# Input_v2_1.net
KiCad netlist of a schematic drawn in EAGLE
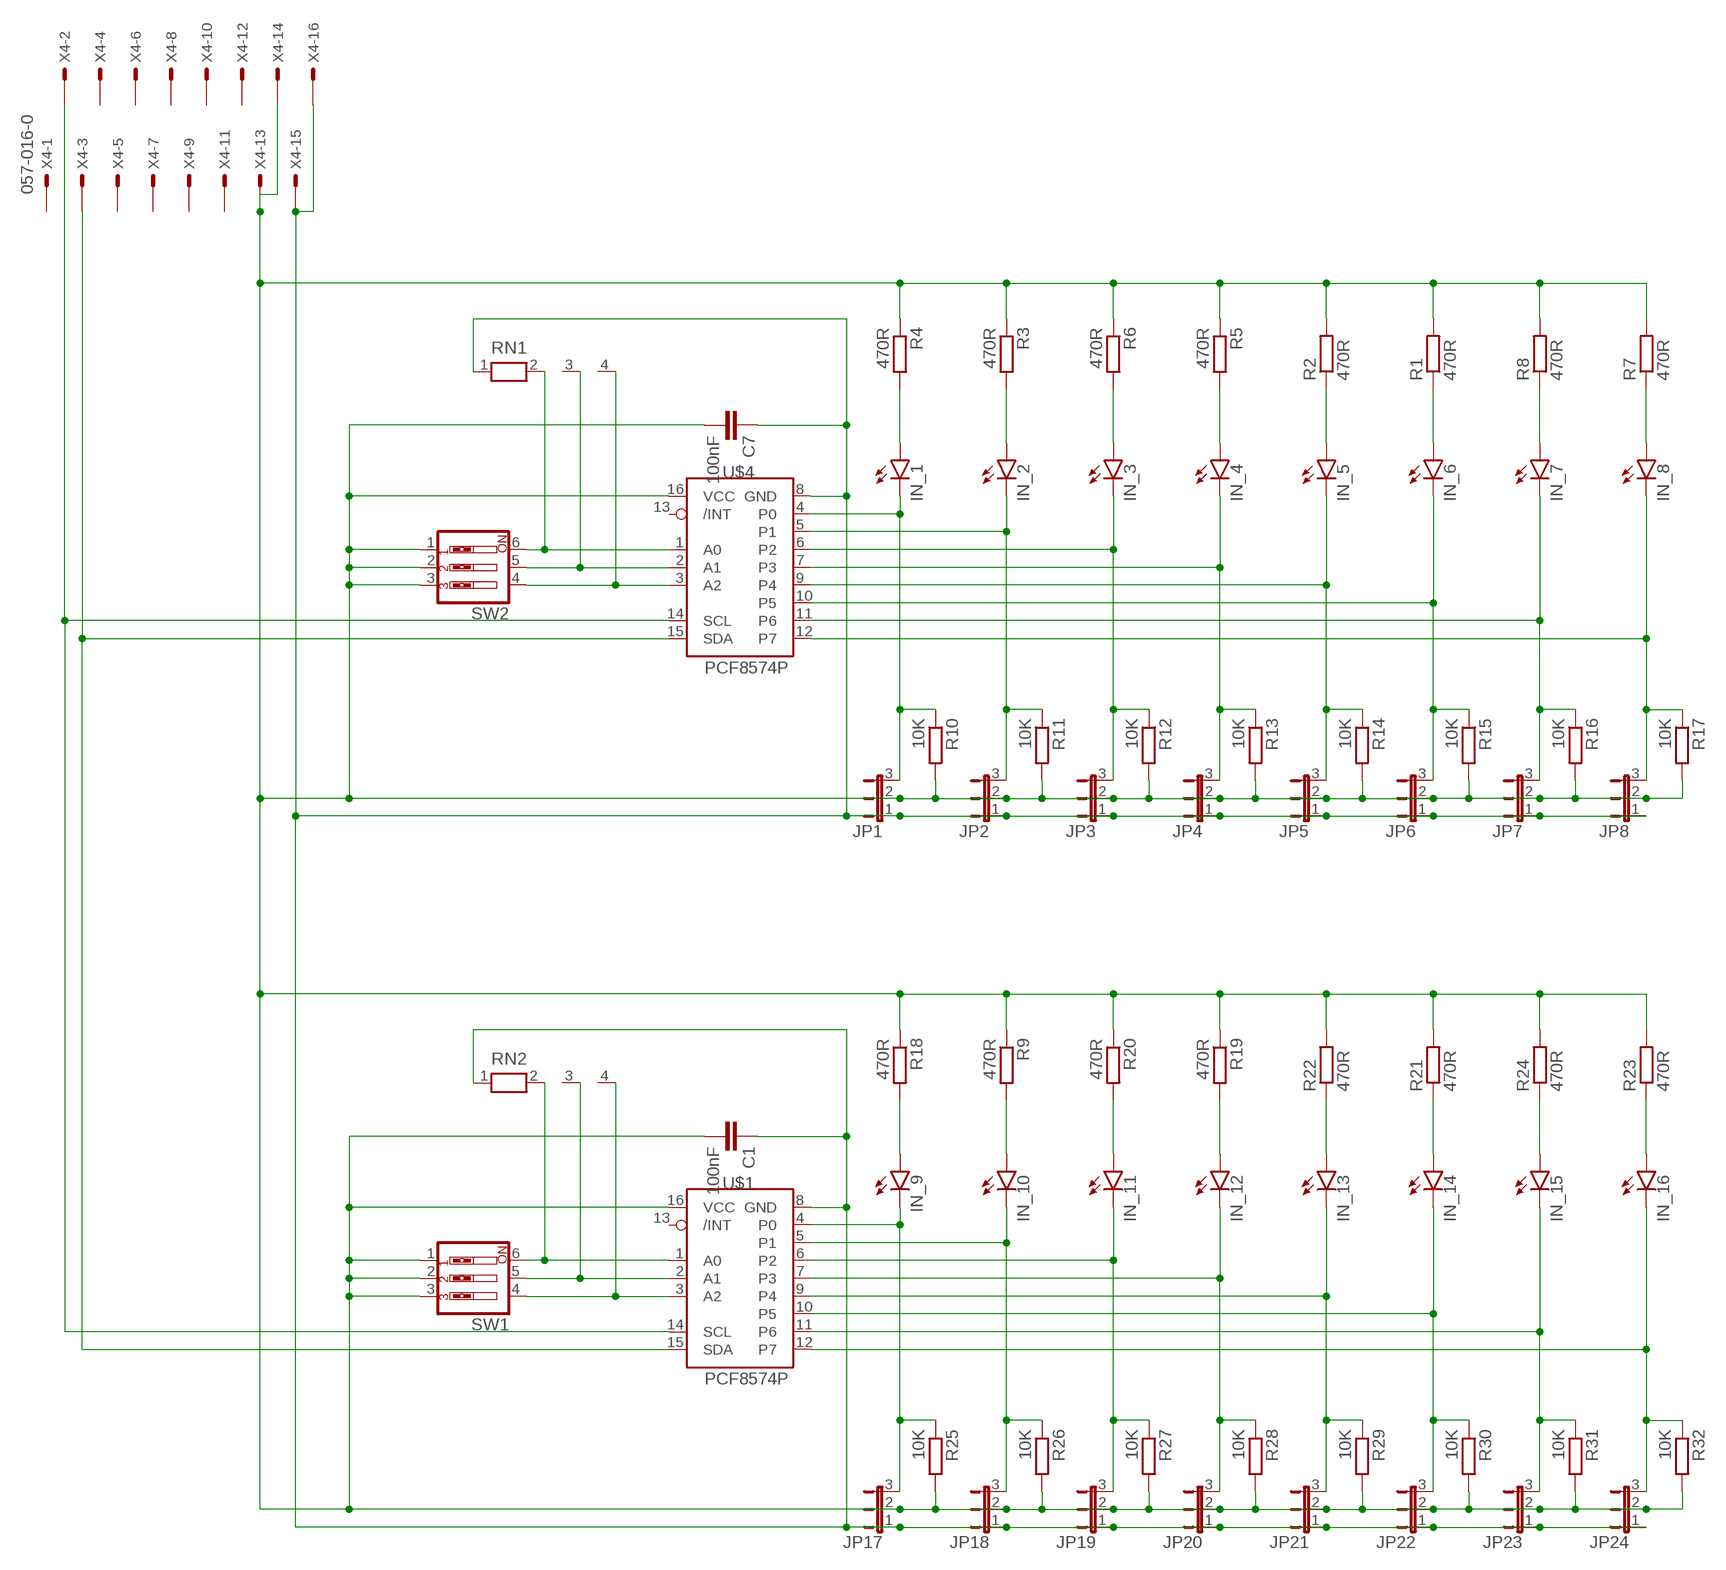
[diagram p0: schematic, sheet 1]

(export (version "E")
  (design (tool "Eeschema 10.0.6"))
  (components
    (comp (ref "C1")
      (value "100nF")
      (footprint "eagle-import:C025-024X044")
      (libsource (lib "eagle-import") (part "C-EU025-024X044"))
    )
    (comp (ref "C7")
      (value "100nF")
      (footprint "eagle-import:C025-024X044")
      (libsource (lib "eagle-import") (part "C-EU025-024X044"))
    )
    (comp (ref "IN_1")
      (value "LED3MM")
      (footprint "eagle-import:LED3MM")
      (libsource (lib "eagle-import") (part "LED3MM"))
    )
    (comp (ref "IN_2")
      (value "LED3MM")
      (footprint "eagle-import:LED3MM")
      (libsource (lib "eagle-import") (part "LED3MM"))
    )
    (comp (ref "IN_3")
      (value "LED3MM")
      (footprint "eagle-import:LED3MM")
      (libsource (lib "eagle-import") (part "LED3MM"))
    )
    (comp (ref "IN_4")
      (value "LED3MM")
      (footprint "eagle-import:LED3MM")
      (libsource (lib "eagle-import") (part "LED3MM"))
    )
    (comp (ref "IN_5")
      (value "LED3MM")
      (footprint "eagle-import:LED3MM")
      (libsource (lib "eagle-import") (part "LED3MM"))
    )
    (comp (ref "IN_6")
      (value "LED3MM")
      (footprint "eagle-import:LED3MM")
      (libsource (lib "eagle-import") (part "LED3MM"))
    )
    (comp (ref "IN_7")
      (value "LED3MM")
      (footprint "eagle-import:LED3MM")
      (libsource (lib "eagle-import") (part "LED3MM"))
    )
    (comp (ref "IN_8")
      (value "LED3MM")
      (footprint "eagle-import:LED3MM")
      (libsource (lib "eagle-import") (part "LED3MM"))
    )
    (comp (ref "IN_9")
      (value "LED3MM")
      (footprint "eagle-import:LED3MM")
      (libsource (lib "eagle-import") (part "LED3MM"))
    )
    (comp (ref "IN_10")
      (value "LED3MM")
      (footprint "eagle-import:LED3MM")
      (libsource (lib "eagle-import") (part "LED3MM"))
    )
    (comp (ref "IN_11")
      (value "LED3MM")
      (footprint "eagle-import:LED3MM")
      (libsource (lib "eagle-import") (part "LED3MM"))
    )
    (comp (ref "IN_12")
      (value "LED3MM")
      (footprint "eagle-import:LED3MM")
      (libsource (lib "eagle-import") (part "LED3MM"))
    )
    (comp (ref "IN_13")
      (value "LED3MM")
      (footprint "eagle-import:LED3MM")
      (libsource (lib "eagle-import") (part "LED3MM"))
    )
    (comp (ref "IN_14")
      (value "LED3MM")
      (footprint "eagle-import:LED3MM")
      (libsource (lib "eagle-import") (part "LED3MM"))
    )
    (comp (ref "IN_15")
      (value "LED3MM")
      (footprint "eagle-import:LED3MM")
      (libsource (lib "eagle-import") (part "LED3MM"))
    )
    (comp (ref "IN_16")
      (value "LED3MM")
      (footprint "eagle-import:LED3MM")
      (libsource (lib "eagle-import") (part "LED3MM"))
    )
    (comp (ref "JP1")
      (value "JP2E")
      (footprint "eagle-import:JP2")
      (libsource (lib "eagle-import") (part "JP2E"))
    )
    (comp (ref "JP2")
      (value "JP2E")
      (footprint "eagle-import:JP2")
      (libsource (lib "eagle-import") (part "JP2E"))
    )
    (comp (ref "JP3")
      (value "JP2E")
      (footprint "eagle-import:JP2")
      (libsource (lib "eagle-import") (part "JP2E"))
    )
    (comp (ref "JP4")
      (value "JP2E")
      (footprint "eagle-import:JP2")
      (libsource (lib "eagle-import") (part "JP2E"))
    )
    (comp (ref "JP5")
      (value "JP2E")
      (footprint "eagle-import:JP2")
      (libsource (lib "eagle-import") (part "JP2E"))
    )
    (comp (ref "JP6")
      (value "JP2E")
      (footprint "eagle-import:JP2")
      (libsource (lib "eagle-import") (part "JP2E"))
    )
    (comp (ref "JP7")
      (value "JP2E")
      (footprint "eagle-import:JP2")
      (libsource (lib "eagle-import") (part "JP2E"))
    )
    (comp (ref "JP8")
      (value "JP2E")
      (footprint "eagle-import:JP2")
      (libsource (lib "eagle-import") (part "JP2E"))
    )
    (comp (ref "JP17")
      (value "JP2E")
      (footprint "eagle-import:JP2")
      (libsource (lib "eagle-import") (part "JP2E"))
    )
    (comp (ref "JP18")
      (value "JP2E")
      (footprint "eagle-import:JP2")
      (libsource (lib "eagle-import") (part "JP2E"))
    )
    (comp (ref "JP19")
      (value "JP2E")
      (footprint "eagle-import:JP2")
      (libsource (lib "eagle-import") (part "JP2E"))
    )
    (comp (ref "JP20")
      (value "JP2E")
      (footprint "eagle-import:JP2")
      (libsource (lib "eagle-import") (part "JP2E"))
    )
    (comp (ref "JP21")
      (value "JP2E")
      (footprint "eagle-import:JP2")
      (libsource (lib "eagle-import") (part "JP2E"))
    )
    (comp (ref "JP22")
      (value "JP2E")
      (footprint "eagle-import:JP2")
      (libsource (lib "eagle-import") (part "JP2E"))
    )
    (comp (ref "JP23")
      (value "JP2E")
      (footprint "eagle-import:JP2")
      (libsource (lib "eagle-import") (part "JP2E"))
    )
    (comp (ref "JP24")
      (value "JP2E")
      (footprint "eagle-import:JP2")
      (libsource (lib "eagle-import") (part "JP2E"))
    )
    (comp (ref "R1")
      (value "470R")
      (footprint "eagle-import:0309_10")
      (libsource (lib "eagle-import") (part "R-EU_0309/10"))
    )
    (comp (ref "R2")
      (value "470R")
      (footprint "eagle-import:0309_10")
      (libsource (lib "eagle-import") (part "R-EU_0309/10"))
    )
    (comp (ref "R3")
      (value "470R")
      (footprint "eagle-import:0309_10")
      (libsource (lib "eagle-import") (part "R-EU_0309/10"))
    )
    (comp (ref "R4")
      (value "470R")
      (footprint "eagle-import:0309_10")
      (libsource (lib "eagle-import") (part "R-EU_0309/10"))
    )
    (comp (ref "R5")
      (value "470R")
      (footprint "eagle-import:0309_10")
      (libsource (lib "eagle-import") (part "R-EU_0309/10"))
    )
    (comp (ref "R6")
      (value "470R")
      (footprint "eagle-import:0309_10")
      (libsource (lib "eagle-import") (part "R-EU_0309/10"))
    )
    (comp (ref "R7")
      (value "470R")
      (footprint "eagle-import:0309_10")
      (libsource (lib "eagle-import") (part "R-EU_0309/10"))
    )
    (comp (ref "R8")
      (value "470R")
      (footprint "eagle-import:0309_10")
      (libsource (lib "eagle-import") (part "R-EU_0309/10"))
    )
    (comp (ref "R9")
      (value "470R")
      (footprint "eagle-import:0309_10")
      (libsource (lib "eagle-import") (part "R-EU_0309/10"))
    )
    (comp (ref "R10")
      (value "10K")
      (footprint "eagle-import:0309_10")
      (libsource (lib "eagle-import") (part "R-EU_0309/10"))
    )
    (comp (ref "R11")
      (value "10K")
      (footprint "eagle-import:0309_10")
      (libsource (lib "eagle-import") (part "R-EU_0309/10"))
    )
    (comp (ref "R12")
      (value "10K")
      (footprint "eagle-import:0309_10")
      (libsource (lib "eagle-import") (part "R-EU_0309/10"))
    )
    (comp (ref "R13")
      (value "10K")
      (footprint "eagle-import:0309_10")
      (libsource (lib "eagle-import") (part "R-EU_0309/10"))
    )
    (comp (ref "R14")
      (value "10K")
      (footprint "eagle-import:0309_10")
      (libsource (lib "eagle-import") (part "R-EU_0309/10"))
    )
    (comp (ref "R15")
      (value "10K")
      (footprint "eagle-import:0309_10")
      (libsource (lib "eagle-import") (part "R-EU_0309/10"))
    )
    (comp (ref "R16")
      (value "10K")
      (footprint "eagle-import:0309_10")
      (libsource (lib "eagle-import") (part "R-EU_0309/10"))
    )
    (comp (ref "R17")
      (value "10K")
      (footprint "eagle-import:0309_10")
      (libsource (lib "eagle-import") (part "R-EU_0309/10"))
    )
    (comp (ref "R18")
      (value "470R")
      (footprint "eagle-import:0309_10")
      (libsource (lib "eagle-import") (part "R-EU_0309/10"))
    )
    (comp (ref "R19")
      (value "470R")
      (footprint "eagle-import:0309_10")
      (libsource (lib "eagle-import") (part "R-EU_0309/10"))
    )
    (comp (ref "R20")
      (value "470R")
      (footprint "eagle-import:0309_10")
      (libsource (lib "eagle-import") (part "R-EU_0309/10"))
    )
    (comp (ref "R21")
      (value "470R")
      (footprint "eagle-import:0309_10")
      (libsource (lib "eagle-import") (part "R-EU_0309/10"))
    )
    (comp (ref "R22")
      (value "470R")
      (footprint "eagle-import:0309_10")
      (libsource (lib "eagle-import") (part "R-EU_0309/10"))
    )
    (comp (ref "R23")
      (value "470R")
      (footprint "eagle-import:0309_10")
      (libsource (lib "eagle-import") (part "R-EU_0309/10"))
    )
    (comp (ref "R24")
      (value "470R")
      (footprint "eagle-import:0309_10")
      (libsource (lib "eagle-import") (part "R-EU_0309/10"))
    )
    (comp (ref "R25")
      (value "10K")
      (footprint "eagle-import:0309_10")
      (libsource (lib "eagle-import") (part "R-EU_0309/10"))
    )
    (comp (ref "R26")
      (value "10K")
      (footprint "eagle-import:0309_10")
      (libsource (lib "eagle-import") (part "R-EU_0309/10"))
    )
    (comp (ref "R27")
      (value "10K")
      (footprint "eagle-import:0309_10")
      (libsource (lib "eagle-import") (part "R-EU_0309/10"))
    )
    (comp (ref "R28")
      (value "10K")
      (footprint "eagle-import:0309_10")
      (libsource (lib "eagle-import") (part "R-EU_0309/10"))
    )
    (comp (ref "R29")
      (value "10K")
      (footprint "eagle-import:0309_10")
      (libsource (lib "eagle-import") (part "R-EU_0309/10"))
    )
    (comp (ref "R30")
      (value "10K")
      (footprint "eagle-import:0309_10")
      (libsource (lib "eagle-import") (part "R-EU_0309/10"))
    )
    (comp (ref "R31")
      (value "10K")
      (footprint "eagle-import:0309_10")
      (libsource (lib "eagle-import") (part "R-EU_0309/10"))
    )
    (comp (ref "R32")
      (value "10K")
      (footprint "eagle-import:0309_10")
      (libsource (lib "eagle-import") (part "R-EU_0309/10"))
    )
    (comp (ref "RN1")
      (value "RN03")
      (footprint "eagle-import:RN-3")
      (libsource (lib "eagle-import") (part "RN03"))
    )
    (comp (ref "RN2")
      (value "RN03")
      (footprint "eagle-import:RN-3")
      (libsource (lib "eagle-import") (part "RN03"))
    )
    (comp (ref "SW1")
      (value "SW_DIP-3")
      (footprint "eagle-import:EDG-03")
      (libsource (lib "eagle-import") (part "SW_DIP-3"))
    )
    (comp (ref "SW2")
      (value "SW_DIP-3")
      (footprint "eagle-import:EDG-03")
      (libsource (lib "eagle-import") (part "SW_DIP-3"))
    )
    (comp (ref "U$1")
      (value "PCF8574P")
      (footprint "eagle-import:DIL16")
      (libsource (lib "eagle-import") (part "PCF8574P"))
    )
    (comp (ref "U$4")
      (value "PCF8574P")
      (footprint "eagle-import:DIL16")
      (libsource (lib "eagle-import") (part "PCF8574P"))
    )
    (comp (ref "X4")
      (value "057-016-0")
      (footprint "eagle-import:057-016-0")
      (libsource (lib "eagle-import") (part "057-016-0"))
    )
  )
  (nets
    (net (code "1") (name "Net-(IN_1-C)") (class "Default")
      (node (ref "IN_1") (pin "K") (pinfunction "C_K") (pintype "passive"))
      (node (ref "JP1") (pin "3") (pinfunction "3_3") (pintype "passive"))
      (node (ref "R10") (pin "1") (pinfunction "1_1") (pintype "passive"))
      (node (ref "U$4") (pin "4") (pinfunction "P0_4") (pintype "bidirectional"))
    )
    (net (code "2") (name "Net-(IN_1-PadA)") (class "Default")
      (node (ref "IN_1") (pin "A") (pinfunction "A_A") (pintype "passive"))
      (node (ref "R4") (pin "2") (pinfunction "2_2") (pintype "passive"))
    )
    (net (code "3") (name "Net-(IN_2-C)") (class "Default")
      (node (ref "IN_2") (pin "K") (pinfunction "C_K") (pintype "passive"))
      (node (ref "JP2") (pin "3") (pinfunction "3_3") (pintype "passive"))
      (node (ref "R11") (pin "1") (pinfunction "1_1") (pintype "passive"))
      (node (ref "U$4") (pin "5") (pinfunction "P1_5") (pintype "bidirectional"))
    )
    (net (code "4") (name "Net-(IN_2-PadA)") (class "Default")
      (node (ref "IN_2") (pin "A") (pinfunction "A_A") (pintype "passive"))
      (node (ref "R3") (pin "2") (pinfunction "2_2") (pintype "passive"))
    )
    (net (code "5") (name "Net-(IN_3-C)") (class "Default")
      (node (ref "IN_3") (pin "K") (pinfunction "C_K") (pintype "passive"))
      (node (ref "JP3") (pin "3") (pinfunction "3_3") (pintype "passive"))
      (node (ref "R12") (pin "1") (pinfunction "1_1") (pintype "passive"))
      (node (ref "U$4") (pin "6") (pinfunction "P2_6") (pintype "bidirectional"))
    )
    (net (code "6") (name "Net-(IN_3-PadA)") (class "Default")
      (node (ref "IN_3") (pin "A") (pinfunction "A_A") (pintype "passive"))
      (node (ref "R6") (pin "2") (pinfunction "2_2") (pintype "passive"))
    )
    (net (code "7") (name "Net-(IN_4-C)") (class "Default")
      (node (ref "IN_4") (pin "K") (pinfunction "C_K") (pintype "passive"))
      (node (ref "JP4") (pin "3") (pinfunction "3_3") (pintype "passive"))
      (node (ref "R13") (pin "1") (pinfunction "1_1") (pintype "passive"))
      (node (ref "U$4") (pin "7") (pinfunction "P3_7") (pintype "bidirectional"))
    )
    (net (code "8") (name "Net-(IN_4-PadA)") (class "Default")
      (node (ref "IN_4") (pin "A") (pinfunction "A_A") (pintype "passive"))
      (node (ref "R5") (pin "2") (pinfunction "2_2") (pintype "passive"))
    )
    (net (code "9") (name "Net-(IN_5-C)") (class "Default")
      (node (ref "IN_5") (pin "K") (pinfunction "C_K") (pintype "passive"))
      (node (ref "JP5") (pin "3") (pinfunction "3_3") (pintype "passive"))
      (node (ref "R14") (pin "1") (pinfunction "1_1") (pintype "passive"))
      (node (ref "U$4") (pin "9") (pinfunction "P4_9") (pintype "bidirectional"))
    )
    (net (code "10") (name "Net-(IN_5-PadA)") (class "Default")
      (node (ref "IN_5") (pin "A") (pinfunction "A_A") (pintype "passive"))
      (node (ref "R2") (pin "1") (pinfunction "1_1") (pintype "passive"))
    )
    (net (code "11") (name "Net-(IN_6-C)") (class "Default")
      (node (ref "IN_6") (pin "K") (pinfunction "C_K") (pintype "passive"))
      (node (ref "JP6") (pin "3") (pinfunction "3_3") (pintype "passive"))
      (node (ref "R15") (pin "1") (pinfunction "1_1") (pintype "passive"))
      (node (ref "U$4") (pin "10") (pinfunction "P5_10") (pintype "bidirectional"))
    )
    (net (code "12") (name "Net-(IN_6-PadA)") (class "Default")
      (node (ref "IN_6") (pin "A") (pinfunction "A_A") (pintype "passive"))
      (node (ref "R1") (pin "1") (pinfunction "1_1") (pintype "passive"))
    )
    (net (code "13") (name "Net-(IN_7-C)") (class "Default")
      (node (ref "IN_7") (pin "K") (pinfunction "C_K") (pintype "passive"))
      (node (ref "JP7") (pin "3") (pinfunction "3_3") (pintype "passive"))
      (node (ref "R16") (pin "1") (pinfunction "1_1") (pintype "passive"))
      (node (ref "U$4") (pin "11") (pinfunction "P6_11") (pintype "bidirectional"))
    )
    (net (code "14") (name "Net-(IN_7-PadA)") (class "Default")
      (node (ref "IN_7") (pin "A") (pinfunction "A_A") (pintype "passive"))
      (node (ref "R8") (pin "1") (pinfunction "1_1") (pintype "passive"))
    )
    (net (code "15") (name "Net-(IN_8-C)") (class "Default")
      (node (ref "IN_8") (pin "K") (pinfunction "C_K") (pintype "passive"))
      (node (ref "JP8") (pin "3") (pinfunction "3_3") (pintype "passive"))
      (node (ref "R17") (pin "1") (pinfunction "1_1") (pintype "passive"))
      (node (ref "U$4") (pin "12") (pinfunction "P7_12") (pintype "bidirectional"))
    )
    (net (code "16") (name "Net-(IN_8-PadA)") (class "Default")
      (node (ref "IN_8") (pin "A") (pinfunction "A_A") (pintype "passive"))
      (node (ref "R7") (pin "1") (pinfunction "1_1") (pintype "passive"))
    )
    (net (code "17") (name "Net-(IN_9-C)") (class "Default")
      (node (ref "IN_9") (pin "K") (pinfunction "C_K") (pintype "passive"))
      (node (ref "JP17") (pin "3") (pinfunction "3_3") (pintype "passive"))
      (node (ref "R25") (pin "1") (pinfunction "1_1") (pintype "passive"))
      (node (ref "U$1") (pin "4") (pinfunction "P0_4") (pintype "bidirectional"))
    )
    (net (code "18") (name "Net-(IN_9-PadA)") (class "Default")
      (node (ref "IN_9") (pin "A") (pinfunction "A_A") (pintype "passive"))
      (node (ref "R18") (pin "2") (pinfunction "2_2") (pintype "passive"))
    )
    (net (code "19") (name "Net-(IN_10-C)") (class "Default")
      (node (ref "IN_10") (pin "K") (pinfunction "C_K") (pintype "passive"))
      (node (ref "JP18") (pin "3") (pinfunction "3_3") (pintype "passive"))
      (node (ref "R26") (pin "1") (pinfunction "1_1") (pintype "passive"))
      (node (ref "U$1") (pin "5") (pinfunction "P1_5") (pintype "bidirectional"))
    )
    (net (code "20") (name "Net-(IN_10-PadA)") (class "Default")
      (node (ref "IN_10") (pin "A") (pinfunction "A_A") (pintype "passive"))
      (node (ref "R9") (pin "2") (pinfunction "2_2") (pintype "passive"))
    )
    (net (code "21") (name "Net-(IN_11-C)") (class "Default")
      (node (ref "IN_11") (pin "K") (pinfunction "C_K") (pintype "passive"))
      (node (ref "JP19") (pin "3") (pinfunction "3_3") (pintype "passive"))
      (node (ref "R27") (pin "1") (pinfunction "1_1") (pintype "passive"))
      (node (ref "U$1") (pin "6") (pinfunction "P2_6") (pintype "bidirectional"))
    )
    (net (code "22") (name "Net-(IN_11-PadA)") (class "Default")
      (node (ref "IN_11") (pin "A") (pinfunction "A_A") (pintype "passive"))
      (node (ref "R20") (pin "2") (pinfunction "2_2") (pintype "passive"))
    )
    (net (code "23") (name "Net-(IN_12-C)") (class "Default")
      (node (ref "IN_12") (pin "K") (pinfunction "C_K") (pintype "passive"))
      (node (ref "JP20") (pin "3") (pinfunction "3_3") (pintype "passive"))
      (node (ref "R28") (pin "1") (pinfunction "1_1") (pintype "passive"))
      (node (ref "U$1") (pin "7") (pinfunction "P3_7") (pintype "bidirectional"))
    )
    (net (code "24") (name "Net-(IN_12-PadA)") (class "Default")
      (node (ref "IN_12") (pin "A") (pinfunction "A_A") (pintype "passive"))
      (node (ref "R19") (pin "2") (pinfunction "2_2") (pintype "passive"))
    )
    (net (code "25") (name "Net-(IN_13-C)") (class "Default")
      (node (ref "IN_13") (pin "K") (pinfunction "C_K") (pintype "passive"))
      (node (ref "JP21") (pin "3") (pinfunction "3_3") (pintype "passive"))
      (node (ref "R29") (pin "1") (pinfunction "1_1") (pintype "passive"))
      (node (ref "U$1") (pin "9") (pinfunction "P4_9") (pintype "bidirectional"))
    )
    (net (code "26") (name "Net-(IN_13-PadA)") (class "Default")
      (node (ref "IN_13") (pin "A") (pinfunction "A_A") (pintype "passive"))
      (node (ref "R22") (pin "1") (pinfunction "1_1") (pintype "passive"))
    )
    (net (code "27") (name "Net-(IN_14-C)") (class "Default")
      (node (ref "IN_14") (pin "K") (pinfunction "C_K") (pintype "passive"))
      (node (ref "JP22") (pin "3") (pinfunction "3_3") (pintype "passive"))
      (node (ref "R30") (pin "1") (pinfunction "1_1") (pintype "passive"))
      (node (ref "U$1") (pin "10") (pinfunction "P5_10") (pintype "bidirectional"))
    )
    (net (code "28") (name "Net-(IN_14-PadA)") (class "Default")
      (node (ref "IN_14") (pin "A") (pinfunction "A_A") (pintype "passive"))
      (node (ref "R21") (pin "1") (pinfunction "1_1") (pintype "passive"))
    )
    (net (code "29") (name "Net-(IN_15-C)") (class "Default")
      (node (ref "IN_15") (pin "K") (pinfunction "C_K") (pintype "passive"))
      (node (ref "JP23") (pin "3") (pinfunction "3_3") (pintype "passive"))
      (node (ref "R31") (pin "1") (pinfunction "1_1") (pintype "passive"))
      (node (ref "U$1") (pin "11") (pinfunction "P6_11") (pintype "bidirectional"))
    )
    (net (code "30") (name "Net-(IN_15-PadA)") (class "Default")
      (node (ref "IN_15") (pin "A") (pinfunction "A_A") (pintype "passive"))
      (node (ref "R24") (pin "1") (pinfunction "1_1") (pintype "passive"))
    )
    (net (code "31") (name "Net-(IN_16-C)") (class "Default")
      (node (ref "IN_16") (pin "K") (pinfunction "C_K") (pintype "passive"))
      (node (ref "JP24") (pin "3") (pinfunction "3_3") (pintype "passive"))
      (node (ref "R32") (pin "1") (pinfunction "1_1") (pintype "passive"))
      (node (ref "U$1") (pin "12") (pinfunction "P7_12") (pintype "bidirectional"))
    )
    (net (code "32") (name "Net-(IN_16-PadA)") (class "Default")
      (node (ref "IN_16") (pin "A") (pinfunction "A_A") (pintype "passive"))
      (node (ref "R23") (pin "1") (pinfunction "1_1") (pintype "passive"))
    )
    (net (code "33") (name "Net-(U$1-A0)") (class "Default")
      (node (ref "RN2") (pin "2") (pinfunction "2_2") (pintype "passive"))
      (node (ref "SW1") (pin "6") (pinfunction "6_6") (pintype "passive"))
      (node (ref "U$1") (pin "1") (pinfunction "A0_1") (pintype "input"))
    )
    (net (code "34") (name "Net-(U$1-A1)") (class "Default")
      (node (ref "RN2") (pin "3") (pinfunction "3_3") (pintype "passive"))
      (node (ref "SW1") (pin "5") (pinfunction "5_5") (pintype "passive"))
      (node (ref "U$1") (pin "2") (pinfunction "A1_2") (pintype "input"))
    )
    (net (code "35") (name "Net-(U$1-A2)") (class "Default")
      (node (ref "RN2") (pin "4") (pinfunction "4_4") (pintype "passive"))
      (node (ref "SW1") (pin "4") (pinfunction "4_4") (pintype "passive"))
      (node (ref "U$1") (pin "3") (pinfunction "A2_3") (pintype "input"))
    )
    (net (code "36") (name "Net-(U$1-GND)") (class "Default")
      (node (ref "C1") (pin "1") (pinfunction "1_1") (pintype "passive"))
      (node (ref "C7") (pin "1") (pinfunction "1_1") (pintype "passive"))
      (node (ref "JP1") (pin "1") (pinfunction "1_1") (pintype "passive"))
      (node (ref "JP17") (pin "1") (pinfunction "1_1") (pintype "passive"))
      (node (ref "JP18") (pin "1") (pinfunction "1_1") (pintype "passive"))
      (node (ref "JP19") (pin "1") (pinfunction "1_1") (pintype "passive"))
      (node (ref "JP2") (pin "1") (pinfunction "1_1") (pintype "passive"))
      (node (ref "JP20") (pin "1") (pinfunction "1_1") (pintype "passive"))
      (node (ref "JP21") (pin "1") (pinfunction "1_1") (pintype "passive"))
      (node (ref "JP22") (pin "1") (pinfunction "1_1") (pintype "passive"))
      (node (ref "JP23") (pin "1") (pinfunction "1_1") (pintype "passive"))
      (node (ref "JP24") (pin "1") (pinfunction "1_1") (pintype "passive"))
      (node (ref "JP3") (pin "1") (pinfunction "1_1") (pintype "passive"))
      (node (ref "JP4") (pin "1") (pinfunction "1_1") (pintype "passive"))
      (node (ref "JP5") (pin "1") (pinfunction "1_1") (pintype "passive"))
      (node (ref "JP6") (pin "1") (pinfunction "1_1") (pintype "passive"))
      (node (ref "JP7") (pin "1") (pinfunction "1_1") (pintype "passive"))
      (node (ref "JP8") (pin "1") (pinfunction "1_1") (pintype "passive"))
      (node (ref "RN1") (pin "1") (pinfunction "1_1") (pintype "passive"))
      (node (ref "RN2") (pin "1") (pinfunction "1_1") (pintype "passive"))
      (node (ref "U$1") (pin "8") (pinfunction "GND_8") (pintype "power_in"))
      (node (ref "U$4") (pin "8") (pinfunction "GND_8") (pintype "power_in"))
      (node (ref "X4") (pin "15") (pinfunction "S_15") (pintype "passive"))
      (node (ref "X4") (pin "16") (pinfunction "S_16") (pintype "passive"))
    )
    (net (code "37") (name "Net-(U$1-SCL)") (class "Default")
      (node (ref "U$1") (pin "14") (pinfunction "SCL_14") (pintype "input"))
      (node (ref "U$4") (pin "14") (pinfunction "SCL_14") (pintype "input"))
      (node (ref "X4") (pin "2") (pinfunction "S_2") (pintype "passive"))
    )
    (net (code "38") (name "Net-(U$1-SDA)") (class "Default")
      (node (ref "U$1") (pin "15") (pinfunction "SDA_15") (pintype "bidirectional"))
      (node (ref "U$4") (pin "15") (pinfunction "SDA_15") (pintype "bidirectional"))
      (node (ref "X4") (pin "3") (pinfunction "S_3") (pintype "passive"))
    )
    (net (code "39") (name "Net-(U$1-VCC)") (class "Default")
      (node (ref "C1") (pin "2") (pinfunction "2_2") (pintype "passive"))
      (node (ref "C7") (pin "2") (pinfunction "2_2") (pintype "passive"))
      (node (ref "JP1") (pin "2") (pinfunction "2_2") (pintype "passive"))
      (node (ref "JP17") (pin "2") (pinfunction "2_2") (pintype "passive"))
      (node (ref "JP18") (pin "2") (pinfunction "2_2") (pintype "passive"))
      (node (ref "JP19") (pin "2") (pinfunction "2_2") (pintype "passive"))
      (node (ref "JP2") (pin "2") (pinfunction "2_2") (pintype "passive"))
      (node (ref "JP20") (pin "2") (pinfunction "2_2") (pintype "passive"))
      (node (ref "JP21") (pin "2") (pinfunction "2_2") (pintype "passive"))
      (node (ref "JP22") (pin "2") (pinfunction "2_2") (pintype "passive"))
      (node (ref "JP23") (pin "2") (pinfunction "2_2") (pintype "passive"))
      (node (ref "JP24") (pin "2") (pinfunction "2_2") (pintype "passive"))
      (node (ref "JP3") (pin "2") (pinfunction "2_2") (pintype "passive"))
      (node (ref "JP4") (pin "2") (pinfunction "2_2") (pintype "passive"))
      (node (ref "JP5") (pin "2") (pinfunction "2_2") (pintype "passive"))
      (node (ref "JP6") (pin "2") (pinfunction "2_2") (pintype "passive"))
      (node (ref "JP7") (pin "2") (pinfunction "2_2") (pintype "passive"))
      (node (ref "JP8") (pin "2") (pinfunction "2_2") (pintype "passive"))
      (node (ref "R1") (pin "2") (pinfunction "2_2") (pintype "passive"))
      (node (ref "R10") (pin "2") (pinfunction "2_2") (pintype "passive"))
      (node (ref "R11") (pin "2") (pinfunction "2_2") (pintype "passive"))
      (node (ref "R12") (pin "2") (pinfunction "2_2") (pintype "passive"))
      (node (ref "R13") (pin "2") (pinfunction "2_2") (pintype "passive"))
      (node (ref "R14") (pin "2") (pinfunction "2_2") (pintype "passive"))
      (node (ref "R15") (pin "2") (pinfunction "2_2") (pintype "passive"))
      (node (ref "R16") (pin "2") (pinfunction "2_2") (pintype "passive"))
      (node (ref "R17") (pin "2") (pinfunction "2_2") (pintype "passive"))
      (node (ref "R18") (pin "1") (pinfunction "1_1") (pintype "passive"))
      (node (ref "R19") (pin "1") (pinfunction "1_1") (pintype "passive"))
      (node (ref "R2") (pin "2") (pinfunction "2_2") (pintype "passive"))
      (node (ref "R20") (pin "1") (pinfunction "1_1") (pintype "passive"))
      (node (ref "R21") (pin "2") (pinfunction "2_2") (pintype "passive"))
      (node (ref "R22") (pin "2") (pinfunction "2_2") (pintype "passive"))
      (node (ref "R23") (pin "2") (pinfunction "2_2") (pintype "passive"))
      (node (ref "R24") (pin "2") (pinfunction "2_2") (pintype "passive"))
      (node (ref "R25") (pin "2") (pinfunction "2_2") (pintype "passive"))
      (node (ref "R26") (pin "2") (pinfunction "2_2") (pintype "passive"))
      (node (ref "R27") (pin "2") (pinfunction "2_2") (pintype "passive"))
      (node (ref "R28") (pin "2") (pinfunction "2_2") (pintype "passive"))
      (node (ref "R29") (pin "2") (pinfunction "2_2") (pintype "passive"))
      (node (ref "R3") (pin "1") (pinfunction "1_1") (pintype "passive"))
      (node (ref "R30") (pin "2") (pinfunction "2_2") (pintype "passive"))
      (node (ref "R31") (pin "2") (pinfunction "2_2") (pintype "passive"))
      (node (ref "R32") (pin "2") (pinfunction "2_2") (pintype "passive"))
      (node (ref "R4") (pin "1") (pinfunction "1_1") (pintype "passive"))
      (node (ref "R5") (pin "1") (pinfunction "1_1") (pintype "passive"))
      (node (ref "R6") (pin "1") (pinfunction "1_1") (pintype "passive"))
      (node (ref "R7") (pin "2") (pinfunction "2_2") (pintype "passive"))
      (node (ref "R8") (pin "2") (pinfunction "2_2") (pintype "passive"))
      (node (ref "R9") (pin "1") (pinfunction "1_1") (pintype "passive"))
      (node (ref "SW1") (pin "1") (pinfunction "1_1") (pintype "passive"))
      (node (ref "SW1") (pin "2") (pinfunction "2_2") (pintype "passive"))
      (node (ref "SW1") (pin "3") (pinfunction "3_3") (pintype "passive"))
      (node (ref "SW2") (pin "1") (pinfunction "1_1") (pintype "passive"))
      (node (ref "SW2") (pin "2") (pinfunction "2_2") (pintype "passive"))
      (node (ref "SW2") (pin "3") (pinfunction "3_3") (pintype "passive"))
      (node (ref "U$1") (pin "16") (pinfunction "VCC_16") (pintype "power_in"))
      (node (ref "U$4") (pin "16") (pinfunction "VCC_16") (pintype "power_in"))
      (node (ref "X4") (pin "13") (pinfunction "S_13") (pintype "passive"))
      (node (ref "X4") (pin "14") (pinfunction "S_14") (pintype "passive"))
    )
    (net (code "40") (name "Net-(U$4-A0)") (class "Default")
      (node (ref "RN1") (pin "2") (pinfunction "2_2") (pintype "passive"))
      (node (ref "SW2") (pin "6") (pinfunction "6_6") (pintype "passive"))
      (node (ref "U$4") (pin "1") (pinfunction "A0_1") (pintype "input"))
    )
    (net (code "41") (name "Net-(U$4-A1)") (class "Default")
      (node (ref "RN1") (pin "3") (pinfunction "3_3") (pintype "passive"))
      (node (ref "SW2") (pin "5") (pinfunction "5_5") (pintype "passive"))
      (node (ref "U$4") (pin "2") (pinfunction "A1_2") (pintype "input"))
    )
    (net (code "42") (name "Net-(U$4-A2)") (class "Default")
      (node (ref "RN1") (pin "4") (pinfunction "4_4") (pintype "passive"))
      (node (ref "SW2") (pin "4") (pinfunction "4_4") (pintype "passive"))
      (node (ref "U$4") (pin "3") (pinfunction "A2_3") (pintype "input"))
    )
    (net (code "43") (name "unconnected-(U$1-{slash}INT-Pad13)") (class "Default")
      (node (ref "U$1") (pin "13") (pinfunction "/INT_13") (pintype "output"))
    )
    (net (code "44") (name "unconnected-(U$4-{slash}INT-Pad13)") (class "Default")
      (node (ref "U$4") (pin "13") (pinfunction "/INT_13") (pintype "output"))
    )
    (net (code "45") (name "unconnected-(X4A-S-Pad1)") (class "Default")
      (node (ref "X4") (pin "1") (pinfunction "S_1") (pintype "passive"))
    )
    (net (code "46") (name "unconnected-(X4B-S-Pad10)") (class "Default")
      (node (ref "X4") (pin "10") (pinfunction "S_10") (pintype "passive"))
    )
    (net (code "47") (name "unconnected-(X4C-S-Pad11)") (class "Default")
      (node (ref "X4") (pin "11") (pinfunction "S_11") (pintype "passive"))
    )
    (net (code "48") (name "unconnected-(X4D-S-Pad12)") (class "Default")
      (node (ref "X4") (pin "12") (pinfunction "S_12") (pintype "passive"))
    )
    (net (code "49") (name "unconnected-(X4K-S-Pad4)") (class "Default")
      (node (ref "X4") (pin "4") (pinfunction "S_4") (pintype "passive"))
    )
    (net (code "50") (name "unconnected-(X4L-S-Pad5)") (class "Default")
      (node (ref "X4") (pin "5") (pinfunction "S_5") (pintype "passive"))
    )
    (net (code "51") (name "unconnected-(X4M-S-Pad6)") (class "Default")
      (node (ref "X4") (pin "6") (pinfunction "S_6") (pintype "passive"))
    )
    (net (code "52") (name "unconnected-(X4N-S-Pad7)") (class "Default")
      (node (ref "X4") (pin "7") (pinfunction "S_7") (pintype "passive"))
    )
    (net (code "53") (name "unconnected-(X4O-S-Pad8)") (class "Default")
      (node (ref "X4") (pin "8") (pinfunction "S_8") (pintype "passive"))
    )
    (net (code "54") (name "unconnected-(X4P-S-Pad9)") (class "Default")
      (node (ref "X4") (pin "9") (pinfunction "S_9") (pintype "passive"))
    )
  )
)
